# Badge_V2.net
KiCad netlist of a schematic drawn in Altium Designer
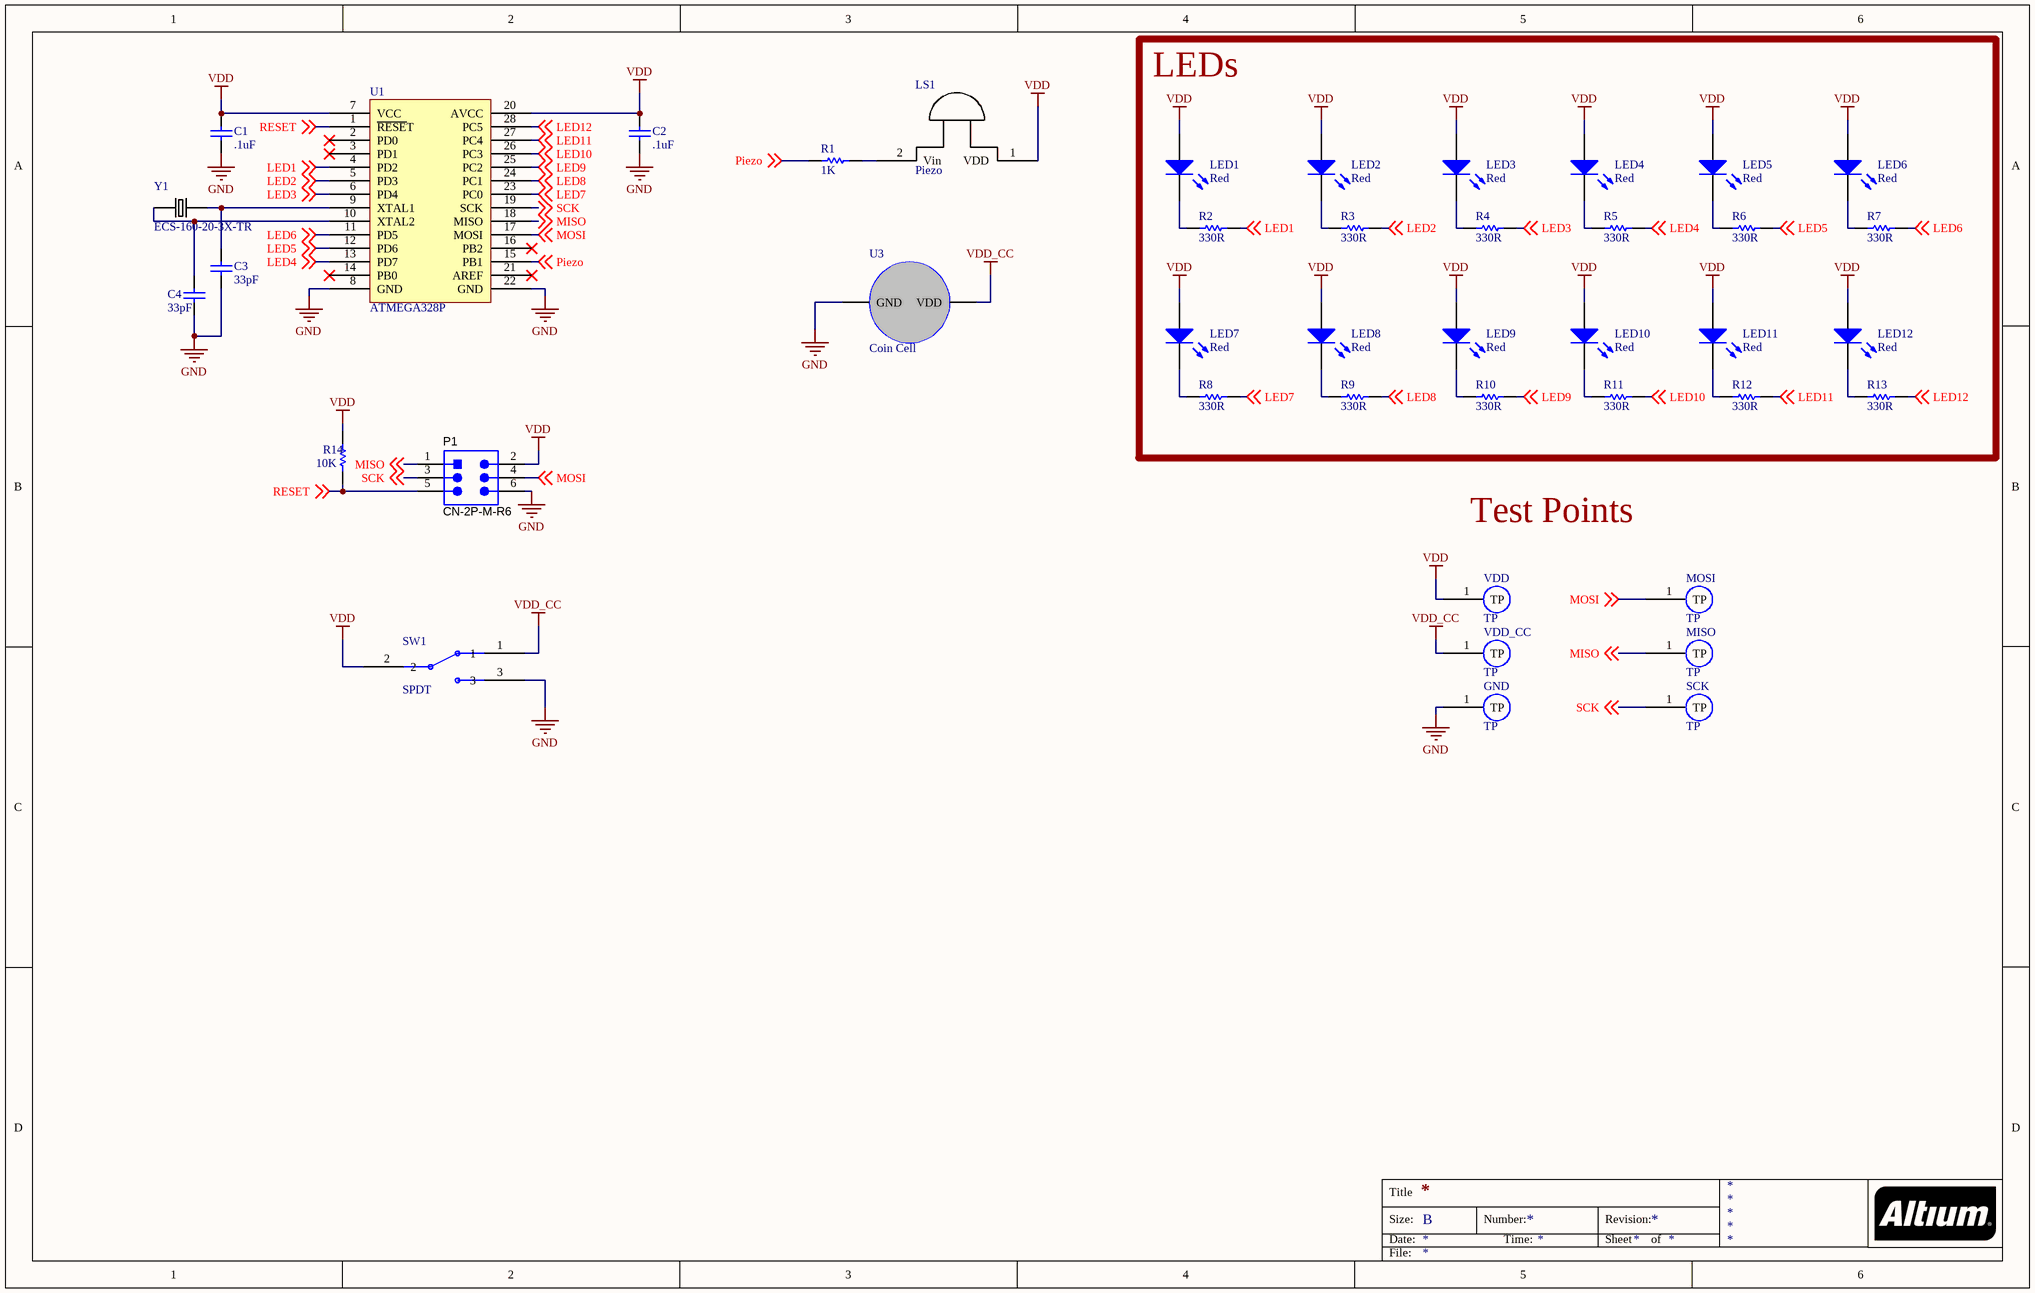
[diagram p0: Badge_V2.SchDoc]

(export (version "E")
  (design (tool "Eeschema 10.0.6"))
  (components
    (comp (ref "C1")
      (value ".1uF")
      (footprint "CAPC0805(2012)145_L")
      (description "capacitor")
      (fields (field (name "MANUFACTURER") "Yageo") (field (name "MPN") "CC0805ZRY5V9BB104"))
      (libsource (lib "Badge_V2") (part "CAP100n"))
    )
    (comp (ref "C2")
      (value ".1uF")
      (footprint "CAPC0805(2012)145_L")
      (description "capacitor")
      (fields (field (name "MANUFACTURER") "Yageo") (field (name "MPN") "CC0805ZRY5V9BB104"))
      (libsource (lib "Badge_V2") (part "CAP100n"))
    )
    (comp (ref "C3")
      (value "33pF")
      (footprint "CAPC0805(2012)145_L")
      (description "CAP CER 33PF 50V C0G/NPO 0805")
      (fields (field (name "MANUFACTURER") "Yageo") (field (name "MPN") "CC0805JRNPO9BN330"))
      (libsource (lib "Badge_V2") (part "CAP33p"))
    )
    (comp (ref "C4")
      (value "33pF")
      (footprint "CAPC0805(2012)145_L")
      (description "CAP CER 33PF 50V C0G/NPO 0805")
      (fields (field (name "MANUFACTURER") "Yageo") (field (name "MPN") "CC0805JRNPO9BN330"))
      (libsource (lib "Badge_V2") (part "CAP33p"))
    )
    (comp (ref "GND")
      (value "TP")
      (footprint "TP")
      (description "Test Point")
      (libsource (lib "Badge_V2") (part "TestPoint"))
    )
    (comp (ref "LED1")
      (value "Red")
      (footprint "LED_0805")
      (description "Red 625nm LED Indication - Discrete 2V 0805 (2012 Metric)")
      (fields (field (name "MPN") "150080RS75000") (field (name "MANUFACTURER") "Würth Elektronik"))
      (libsource (lib "Badge_V2") (part "LED_0805"))
    )
    (comp (ref "LED2")
      (value "Red")
      (footprint "LED_0805")
      (description "Red 625nm LED Indication - Discrete 2V 0805 (2012 Metric)")
      (fields (field (name "MPN") "150080RS75000") (field (name "MANUFACTURER") "Würth Elektronik"))
      (libsource (lib "Badge_V2") (part "LED_0805"))
    )
    (comp (ref "LED3")
      (value "Red")
      (footprint "LED_0805")
      (description "Red 625nm LED Indication - Discrete 2V 0805 (2012 Metric)")
      (fields (field (name "MPN") "150080RS75000") (field (name "MANUFACTURER") "Würth Elektronik"))
      (libsource (lib "Badge_V2") (part "LED_0805"))
    )
    (comp (ref "LED4")
      (value "Red")
      (footprint "LED_0805")
      (description "Red 625nm LED Indication - Discrete 2V 0805 (2012 Metric)")
      (fields (field (name "MPN") "150080RS75000") (field (name "MANUFACTURER") "Würth Elektronik"))
      (libsource (lib "Badge_V2") (part "LED_0805"))
    )
    (comp (ref "LED5")
      (value "Red")
      (footprint "LED_0805")
      (description "Red 625nm LED Indication - Discrete 2V 0805 (2012 Metric)")
      (fields (field (name "MPN") "150080RS75000") (field (name "MANUFACTURER") "Würth Elektronik"))
      (libsource (lib "Badge_V2") (part "LED_0805"))
    )
    (comp (ref "LED6")
      (value "Red")
      (footprint "LED_0805")
      (description "Red 625nm LED Indication - Discrete 2V 0805 (2012 Metric)")
      (fields (field (name "MPN") "150080RS75000") (field (name "MANUFACTURER") "Würth Elektronik"))
      (libsource (lib "Badge_V2") (part "LED_0805"))
    )
    (comp (ref "LED7")
      (value "Red")
      (footprint "LED_0805")
      (description "Red 625nm LED Indication - Discrete 2V 0805 (2012 Metric)")
      (fields (field (name "MPN") "150080RS75000") (field (name "MANUFACTURER") "Würth Elektronik"))
      (libsource (lib "Badge_V2") (part "LED_0805"))
    )
    (comp (ref "LED8")
      (value "Red")
      (footprint "LED_0805")
      (description "Red 625nm LED Indication - Discrete 2V 0805 (2012 Metric)")
      (fields (field (name "MPN") "150080RS75000") (field (name "MANUFACTURER") "Würth Elektronik"))
      (libsource (lib "Badge_V2") (part "LED_0805"))
    )
    (comp (ref "LED9")
      (value "Red")
      (footprint "LED_0805")
      (description "Red 625nm LED Indication - Discrete 2V 0805 (2012 Metric)")
      (fields (field (name "MPN") "150080RS75000") (field (name "MANUFACTURER") "Würth Elektronik"))
      (libsource (lib "Badge_V2") (part "LED_0805"))
    )
    (comp (ref "LED10")
      (value "Red")
      (footprint "LED_0805")
      (description "Red 625nm LED Indication - Discrete 2V 0805 (2012 Metric)")
      (fields (field (name "MPN") "150080RS75000") (field (name "MANUFACTURER") "Würth Elektronik"))
      (libsource (lib "Badge_V2") (part "LED_0805"))
    )
    (comp (ref "LED11")
      (value "Red")
      (footprint "LED_0805")
      (description "Red 625nm LED Indication - Discrete 2V 0805 (2012 Metric)")
      (fields (field (name "MPN") "150080RS75000") (field (name "MANUFACTURER") "Würth Elektronik"))
      (libsource (lib "Badge_V2") (part "LED_0805"))
    )
    (comp (ref "LED12")
      (value "Red")
      (footprint "LED_0805")
      (description "Red 625nm LED Indication - Discrete 2V 0805 (2012 Metric)")
      (fields (field (name "MPN") "150080RS75000") (field (name "MANUFACTURER") "Würth Elektronik"))
      (libsource (lib "Badge_V2") (part "LED_0805"))
    )
    (comp (ref "LS1")
      (value "Piezo")
      (footprint "Piezo")
      (description "AUDIO PIEZO TRANSDUCER 30V TH")
      (fields (field (name "MPN") "PS1240P02BT") (field (name "MANUFACTURER") "TDK Corporation"))
      (libsource (lib "Badge_V2") (part "Piezo"))
    )
    (comp (ref "MISO")
      (value "TP")
      (footprint "TP")
      (description "Test Point")
      (libsource (lib "Badge_V2") (part "TestPoint"))
    )
    (comp (ref "MOSI")
      (value "TP")
      (footprint "TP")
      (description "Test Point")
      (libsource (lib "Badge_V2") (part "TestPoint"))
    )
    (comp (ref "P1")
      (value "CN-2P-M-R6")
      (footprint "HRWN-M20-9980346_V")
      (libsource (lib "Badge_V2") (part "CN-2P-M-R6"))
    )
    (comp (ref "R1")
      (value "1K")
      (footprint "RESC0805(2012)_M")
      (description "RES SMD 1K OHM 5% 1/8W 0805")
      (fields (field (name "MANUFACTURER") "Yageo") (field (name "MPN") "RC0805JR-071KL"))
      (libsource (lib "Badge_V2") (part "RES"))
    )
    (comp (ref "R2")
      (value "330R")
      (footprint "RESC0805(2012)_M")
      (description "RES SMD 330 OHM 5% 1/8W 0805")
      (fields (field (name "MANUFACTURER") "Yageo") (field (name "MPN") "RC0805JR07330RL"))
      (libsource (lib "Badge_V2") (part "RES"))
    )
    (comp (ref "R3")
      (value "330R")
      (footprint "RESC0805(2012)_M")
      (description "RES SMD 330 OHM 5% 1/8W 0805")
      (fields (field (name "MANUFACTURER") "Yageo") (field (name "MPN") "RC0805JR07330RL"))
      (libsource (lib "Badge_V2") (part "RES"))
    )
    (comp (ref "R4")
      (value "330R")
      (footprint "RESC0805(2012)_M")
      (description "RES SMD 330 OHM 5% 1/8W 0805")
      (fields (field (name "MANUFACTURER") "Yageo") (field (name "MPN") "RC0805JR07330RL"))
      (libsource (lib "Badge_V2") (part "RES"))
    )
    (comp (ref "R5")
      (value "330R")
      (footprint "RESC0805(2012)_M")
      (description "RES SMD 330 OHM 5% 1/8W 0805")
      (fields (field (name "MANUFACTURER") "Yageo") (field (name "MPN") "RC0805JR07330RL"))
      (libsource (lib "Badge_V2") (part "RES"))
    )
    (comp (ref "R6")
      (value "330R")
      (footprint "RESC0805(2012)_M")
      (description "RES SMD 330 OHM 5% 1/8W 0805")
      (fields (field (name "MANUFACTURER") "Yageo") (field (name "MPN") "RC0805JR07330RL"))
      (libsource (lib "Badge_V2") (part "RES"))
    )
    (comp (ref "R7")
      (value "330R")
      (footprint "RESC0805(2012)_M")
      (description "RES SMD 330 OHM 5% 1/8W 0805")
      (fields (field (name "MANUFACTURER") "Yageo") (field (name "MPN") "RC0805JR07330RL"))
      (libsource (lib "Badge_V2") (part "RES"))
    )
    (comp (ref "R8")
      (value "330R")
      (footprint "RESC0805(2012)_M")
      (description "RES SMD 330 OHM 5% 1/8W 0805")
      (fields (field (name "MANUFACTURER") "Yageo") (field (name "MPN") "RC0805JR07330RL"))
      (libsource (lib "Badge_V2") (part "RES"))
    )
    (comp (ref "R9")
      (value "330R")
      (footprint "RESC0805(2012)_M")
      (description "RES SMD 330 OHM 5% 1/8W 0805")
      (fields (field (name "MANUFACTURER") "Yageo") (field (name "MPN") "RC0805JR07330RL"))
      (libsource (lib "Badge_V2") (part "RES"))
    )
    (comp (ref "R10")
      (value "330R")
      (footprint "RESC0805(2012)_M")
      (description "RES SMD 330 OHM 5% 1/8W 0805")
      (fields (field (name "MANUFACTURER") "Yageo") (field (name "MPN") "RC0805JR07330RL"))
      (libsource (lib "Badge_V2") (part "RES"))
    )
    (comp (ref "R11")
      (value "330R")
      (footprint "RESC0805(2012)_M")
      (description "RES SMD 330 OHM 5% 1/8W 0805")
      (fields (field (name "MANUFACTURER") "Yageo") (field (name "MPN") "RC0805JR07330RL"))
      (libsource (lib "Badge_V2") (part "RES"))
    )
    (comp (ref "R12")
      (value "330R")
      (footprint "RESC0805(2012)_M")
      (description "RES SMD 330 OHM 5% 1/8W 0805")
      (fields (field (name "MANUFACTURER") "Yageo") (field (name "MPN") "RC0805JR07330RL"))
      (libsource (lib "Badge_V2") (part "RES"))
    )
    (comp (ref "R13")
      (value "330R")
      (footprint "RESC0805(2012)_M")
      (description "RES SMD 330 OHM 5% 1/8W 0805")
      (fields (field (name "MANUFACTURER") "Yageo") (field (name "MPN") "RC0805JR07330RL"))
      (libsource (lib "Badge_V2") (part "RES"))
    )
    (comp (ref "R14")
      (value "10K")
      (footprint "RESC0805(2012)_M")
      (description "RES SMD 10K OHM 5% 1/8W 0805")
      (fields (field (name "MANUFACTURER") "Yageo") (field (name "MPN") "RC0603JR-0710KL"))
      (libsource (lib "Badge_V2") (part "RES10K"))
    )
    (comp (ref "SCK")
      (value "TP")
      (footprint "TP")
      (description "Test Point")
      (libsource (lib "Badge_V2") (part "TestPoint"))
    )
    (comp (ref "SW1")
      (value "SPDT")
      (footprint "EG1218_EG1218")
      (description "Slide Switch SPDT Through Hole")
      (fields (field (name "MPN") "EG1218") (field (name "MANUFACTURER") "E-Switch"))
      (libsource (lib "Badge_V2") (part "SPDT_Switch"))
    )
    (comp (ref "U1")
      (value "ATMEGA328P")
      (footprint "1-2199298-9")
      (description "AVR AVR® ATmega Microcontroller IC 8-Bit 20MHz 32KB (16K x 16) FLASH 28-PDIP")
      (fields (field (name "MANUFACTURER") "Microchip Technology") (field (name "MPN") "ATMEGA328P-PU"))
      (libsource (lib "Badge_V2") (part "ATMEGA328P-PU"))
    )
    (comp (ref "U3")
      (value "Coin Cell")
      (footprint "Batt")
      (description "Battery Retainer Coin, 20.0mm 1 Cell SMD (SMT) Tab")
      (fields (field (name "MPN") "3034TR") (field (name "MANUFACTURER") "Keystone Electronics"))
      (libsource (lib "badge") (part "Batt"))
    )
    (comp (ref "VDD")
      (value "TP")
      (footprint "TP")
      (description "Test Point")
      (libsource (lib "Badge_V2") (part "TestPoint"))
    )
    (comp (ref "VDD_CC")
      (value "TP")
      (footprint "TP")
      (description "Test Point")
      (libsource (lib "Badge_V2") (part "TestPoint"))
    )
    (comp (ref "Y1")
      (value "ECS-160-20-3X-TR")
      (footprint "XTAL_ECS-160-20-3X-TR")
      (description "16MHz Â±30ppm Crystal 20pF 50 Ohms HC-49/US")
      (fields (field (name "MF") "ECS Inc.") (field (name "DIGI-KEY_PART_NUMBER") "XC1776CT-ND"))
      (libsource (lib "Badge_V2") (part "ECS-160-20-3X-TR"))
    )
  )
  (nets
    (net (code "1") (name "GND") (class "Default")
      (node (ref "C1") (pin "1") (pinfunction "1_1") (pintype "passive"))
      (node (ref "C2") (pin "1") (pinfunction "1_1") (pintype "passive"))
      (node (ref "C3") (pin "1") (pinfunction "1_1") (pintype "passive"))
      (node (ref "C4") (pin "1") (pinfunction "1_1") (pintype "passive"))
      (node (ref "GND") (pin "1") (pinfunction "TP_1") (pintype "passive"))
      (node (ref "P1") (pin "6") (pinfunction "6_6") (pintype "passive"))
      (node (ref "SW1") (pin "3") (pinfunction "3_3") (pintype "passive"))
      (node (ref "U1") (pin "22") (pinfunction "GND_22") (pintype "passive"))
      (node (ref "U1") (pin "8") (pinfunction "GND_8") (pintype "passive"))
      (node (ref "U3") (pin "GND") (pinfunction "GND_GND") (pintype "passive"))
    )
    (net (code "2") (name "LED1") (class "Default")
      (node (ref "R2") (pin "2") (pinfunction "2_2") (pintype "passive"))
      (node (ref "U1") (pin "4") (pinfunction "PD2_4") (pintype "passive"))
    )
    (net (code "3") (name "LED2") (class "Default")
      (node (ref "R3") (pin "2") (pinfunction "2_2") (pintype "passive"))
      (node (ref "U1") (pin "5") (pinfunction "PD3_5") (pintype "passive"))
    )
    (net (code "4") (name "LED3") (class "Default")
      (node (ref "R4") (pin "2") (pinfunction "2_2") (pintype "passive"))
      (node (ref "U1") (pin "6") (pinfunction "PD4_6") (pintype "passive"))
    )
    (net (code "5") (name "LED4") (class "Default")
      (node (ref "R5") (pin "2") (pinfunction "2_2") (pintype "passive"))
      (node (ref "U1") (pin "13") (pinfunction "PD7_13") (pintype "passive"))
    )
    (net (code "6") (name "LED5") (class "Default")
      (node (ref "R6") (pin "2") (pinfunction "2_2") (pintype "passive"))
      (node (ref "U1") (pin "12") (pinfunction "PD6_12") (pintype "passive"))
    )
    (net (code "7") (name "LED6") (class "Default")
      (node (ref "R7") (pin "2") (pinfunction "2_2") (pintype "passive"))
      (node (ref "U1") (pin "11") (pinfunction "PD5_11") (pintype "passive"))
    )
    (net (code "8") (name "LED7") (class "Default")
      (node (ref "R8") (pin "2") (pinfunction "2_2") (pintype "passive"))
      (node (ref "U1") (pin "23") (pinfunction "PC0_23") (pintype "passive"))
    )
    (net (code "9") (name "LED8") (class "Default")
      (node (ref "R9") (pin "2") (pinfunction "2_2") (pintype "passive"))
      (node (ref "U1") (pin "24") (pinfunction "PC1_24") (pintype "passive"))
    )
    (net (code "10") (name "LED9") (class "Default")
      (node (ref "R10") (pin "2") (pinfunction "2_2") (pintype "passive"))
      (node (ref "U1") (pin "25") (pinfunction "PC2_25") (pintype "passive"))
    )
    (net (code "11") (name "LED10") (class "Default")
      (node (ref "R11") (pin "2") (pinfunction "2_2") (pintype "passive"))
      (node (ref "U1") (pin "26") (pinfunction "PC3_26") (pintype "passive"))
    )
    (net (code "12") (name "LED11") (class "Default")
      (node (ref "R12") (pin "2") (pinfunction "2_2") (pintype "passive"))
      (node (ref "U1") (pin "27") (pinfunction "PC4_27") (pintype "passive"))
    )
    (net (code "13") (name "LED12") (class "Default")
      (node (ref "R13") (pin "2") (pinfunction "2_2") (pintype "passive"))
      (node (ref "U1") (pin "28") (pinfunction "PC5_28") (pintype "passive"))
    )
    (net (code "14") (name "MISO") (class "Default")
      (node (ref "MISO") (pin "1") (pinfunction "TP_1") (pintype "passive"))
      (node (ref "P1") (pin "1") (pinfunction "1_1") (pintype "passive"))
      (node (ref "U1") (pin "18") (pinfunction "MISO_18") (pintype "passive"))
    )
    (net (code "15") (name "MOSI") (class "Default")
      (node (ref "MOSI") (pin "1") (pinfunction "TP_1") (pintype "passive"))
      (node (ref "P1") (pin "4") (pinfunction "4_4") (pintype "passive"))
      (node (ref "U1") (pin "17") (pinfunction "MOSI_17") (pintype "passive"))
    )
    (net (code "16") (name "Net-(LED1-K)") (class "Default")
      (node (ref "LED1") (pin "1") (pinfunction "K_1") (pintype "passive"))
      (node (ref "R2") (pin "1") (pinfunction "1_1") (pintype "passive"))
    )
    (net (code "17") (name "Net-(LED2-K)") (class "Default")
      (node (ref "LED2") (pin "1") (pinfunction "K_1") (pintype "passive"))
      (node (ref "R3") (pin "1") (pinfunction "1_1") (pintype "passive"))
    )
    (net (code "18") (name "Net-(LED3-K)") (class "Default")
      (node (ref "LED3") (pin "1") (pinfunction "K_1") (pintype "passive"))
      (node (ref "R4") (pin "1") (pinfunction "1_1") (pintype "passive"))
    )
    (net (code "19") (name "Net-(LED4-K)") (class "Default")
      (node (ref "LED4") (pin "1") (pinfunction "K_1") (pintype "passive"))
      (node (ref "R5") (pin "1") (pinfunction "1_1") (pintype "passive"))
    )
    (net (code "20") (name "Net-(LED5-K)") (class "Default")
      (node (ref "LED5") (pin "1") (pinfunction "K_1") (pintype "passive"))
      (node (ref "R6") (pin "1") (pinfunction "1_1") (pintype "passive"))
    )
    (net (code "21") (name "Net-(LED6-K)") (class "Default")
      (node (ref "LED6") (pin "1") (pinfunction "K_1") (pintype "passive"))
      (node (ref "R7") (pin "1") (pinfunction "1_1") (pintype "passive"))
    )
    (net (code "22") (name "Net-(LED7-K)") (class "Default")
      (node (ref "LED7") (pin "1") (pinfunction "K_1") (pintype "passive"))
      (node (ref "R8") (pin "1") (pinfunction "1_1") (pintype "passive"))
    )
    (net (code "23") (name "Net-(LED8-K)") (class "Default")
      (node (ref "LED8") (pin "1") (pinfunction "K_1") (pintype "passive"))
      (node (ref "R9") (pin "1") (pinfunction "1_1") (pintype "passive"))
    )
    (net (code "24") (name "Net-(LED9-K)") (class "Default")
      (node (ref "LED9") (pin "1") (pinfunction "K_1") (pintype "passive"))
      (node (ref "R10") (pin "1") (pinfunction "1_1") (pintype "passive"))
    )
    (net (code "25") (name "Net-(LED10-K)") (class "Default")
      (node (ref "LED10") (pin "1") (pinfunction "K_1") (pintype "passive"))
      (node (ref "R11") (pin "1") (pinfunction "1_1") (pintype "passive"))
    )
    (net (code "26") (name "Net-(LED11-K)") (class "Default")
      (node (ref "LED11") (pin "1") (pinfunction "K_1") (pintype "passive"))
      (node (ref "R12") (pin "1") (pinfunction "1_1") (pintype "passive"))
    )
    (net (code "27") (name "Net-(LED12-K)") (class "Default")
      (node (ref "LED12") (pin "1") (pinfunction "K_1") (pintype "passive"))
      (node (ref "R13") (pin "1") (pinfunction "1_1") (pintype "passive"))
    )
    (net (code "28") (name "Net-(LS1-Vin)") (class "Default")
      (node (ref "LS1") (pin "2") (pinfunction "Vin_2") (pintype "passive"))
      (node (ref "R1") (pin "2") (pinfunction "2_2") (pintype "passive"))
    )
    (net (code "29") (name "Net-(U1-XTAL1)") (class "Default")
      (node (ref "C3") (pin "2") (pinfunction "2_2") (pintype "passive"))
      (node (ref "U1") (pin "9") (pinfunction "XTAL1_9") (pintype "passive"))
      (node (ref "Y1") (pin "2") (pinfunction "2_2") (pintype "passive"))
    )
    (net (code "30") (name "Net-(U1-XTAL2)") (class "Default")
      (node (ref "C4") (pin "2") (pinfunction "2_2") (pintype "passive"))
      (node (ref "U1") (pin "10") (pinfunction "XTAL2_10") (pintype "passive"))
      (node (ref "Y1") (pin "1") (pinfunction "1_1") (pintype "passive"))
    )
    (net (code "31") (name "Piezo") (class "Default")
      (node (ref "R1") (pin "1") (pinfunction "1_1") (pintype "passive"))
      (node (ref "U1") (pin "15") (pinfunction "PB1_15") (pintype "passive"))
    )
    (net (code "32") (name "RESET") (class "Default")
      (node (ref "P1") (pin "5") (pinfunction "5_5") (pintype "passive"))
      (node (ref "R14") (pin "2") (pinfunction "2_2") (pintype "passive"))
      (node (ref "U1") (pin "1") (pinfunction "~{RESE}T_1") (pintype "passive"))
    )
    (net (code "33") (name "SCK") (class "Default")
      (node (ref "P1") (pin "3") (pinfunction "3_3") (pintype "passive"))
      (node (ref "SCK") (pin "1") (pinfunction "TP_1") (pintype "passive"))
      (node (ref "U1") (pin "19") (pinfunction "SCK_19") (pintype "passive"))
    )
    (net (code "34") (name "VDD") (class "Default")
      (node (ref "C1") (pin "2") (pinfunction "2_2") (pintype "passive"))
      (node (ref "C2") (pin "2") (pinfunction "2_2") (pintype "passive"))
      (node (ref "LED1") (pin "2") (pinfunction "A_2") (pintype "passive"))
      (node (ref "LED10") (pin "2") (pinfunction "A_2") (pintype "passive"))
      (node (ref "LED11") (pin "2") (pinfunction "A_2") (pintype "passive"))
      (node (ref "LED12") (pin "2") (pinfunction "A_2") (pintype "passive"))
      (node (ref "LED2") (pin "2") (pinfunction "A_2") (pintype "passive"))
      (node (ref "LED3") (pin "2") (pinfunction "A_2") (pintype "passive"))
      (node (ref "LED4") (pin "2") (pinfunction "A_2") (pintype "passive"))
      (node (ref "LED5") (pin "2") (pinfunction "A_2") (pintype "passive"))
      (node (ref "LED6") (pin "2") (pinfunction "A_2") (pintype "passive"))
      (node (ref "LED7") (pin "2") (pinfunction "A_2") (pintype "passive"))
      (node (ref "LED8") (pin "2") (pinfunction "A_2") (pintype "passive"))
      (node (ref "LED9") (pin "2") (pinfunction "A_2") (pintype "passive"))
      (node (ref "LS1") (pin "1") (pinfunction "VDD_1") (pintype "passive"))
      (node (ref "P1") (pin "2") (pinfunction "2_2") (pintype "passive"))
      (node (ref "R14") (pin "1") (pinfunction "1_1") (pintype "passive"))
      (node (ref "SW1") (pin "2") (pinfunction "2_2") (pintype "passive"))
      (node (ref "U1") (pin "20") (pinfunction "AVCC_20") (pintype "passive"))
      (node (ref "U1") (pin "7") (pinfunction "VCC_7") (pintype "passive"))
      (node (ref "VDD") (pin "1") (pinfunction "TP_1") (pintype "passive"))
    )
    (net (code "35") (name "VDD_CC") (class "Default")
      (node (ref "SW1") (pin "1") (pinfunction "1_1") (pintype "passive"))
      (node (ref "U3") (pin "VDD") (pinfunction "VDD_VDD") (pintype "passive"))
      (node (ref "VDD_CC") (pin "1") (pinfunction "TP_1") (pintype "passive"))
    )
    (net (code "36") (name "unconnected-(U1-AREF-Pad21)") (class "Default")
      (node (ref "U1") (pin "21") (pinfunction "AREF_21") (pintype "passive+no_connect"))
    )
    (net (code "37") (name "unconnected-(U1-PB0-Pad14)") (class "Default")
      (node (ref "U1") (pin "14") (pinfunction "PB0_14") (pintype "passive+no_connect"))
    )
    (net (code "38") (name "unconnected-(U1-PB2-Pad16)") (class "Default")
      (node (ref "U1") (pin "16") (pinfunction "PB2_16") (pintype "passive+no_connect"))
    )
    (net (code "39") (name "unconnected-(U1-PD0-Pad2)") (class "Default")
      (node (ref "U1") (pin "2") (pinfunction "PD0_2") (pintype "passive+no_connect"))
    )
    (net (code "40") (name "unconnected-(U1-PD1-Pad3)") (class "Default")
      (node (ref "U1") (pin "3") (pinfunction "PD1_3") (pintype "passive+no_connect"))
    )
  )
)
